# IotaWatt4_8.net
KiCad netlist of a schematic drawn in EAGLE
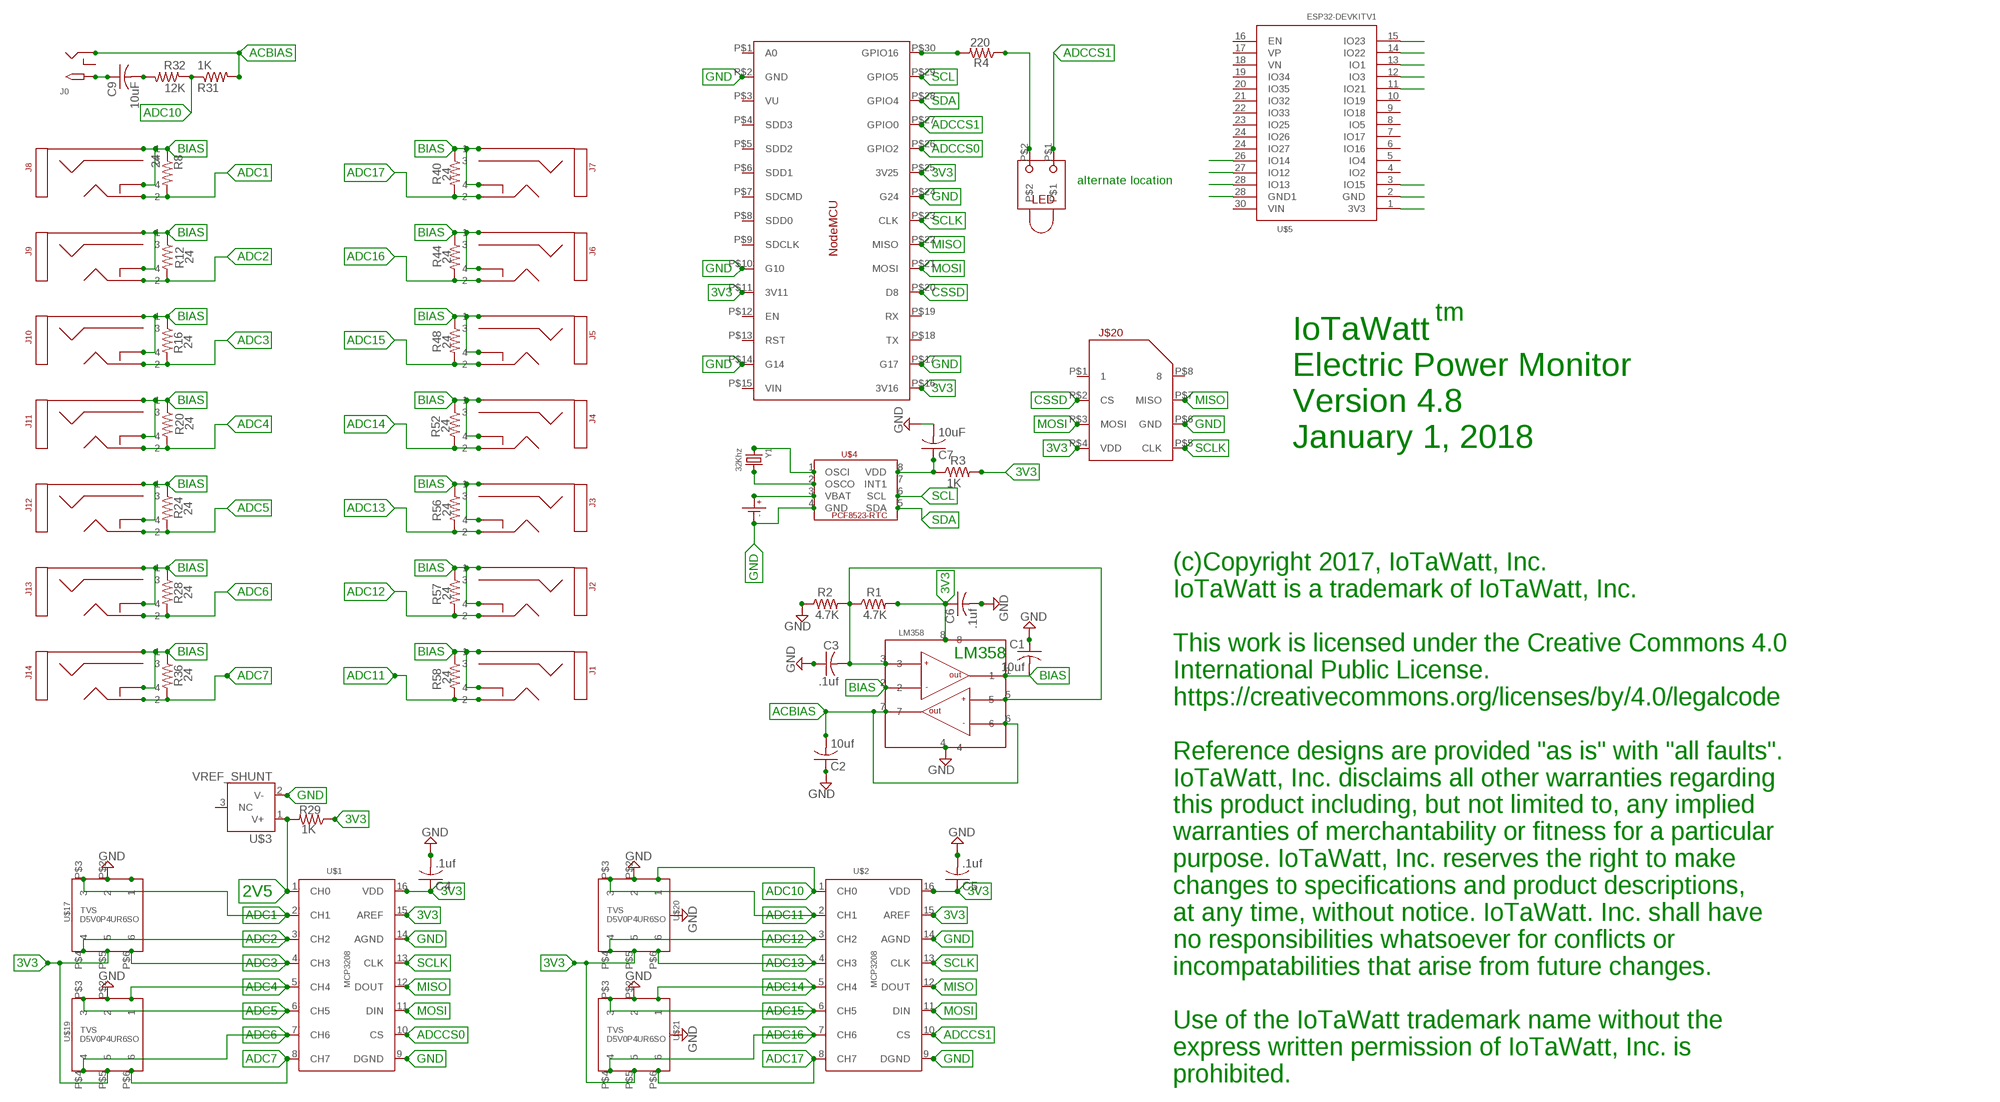
[diagram p0: schematic, sheet 1]

(export (version "E")
  (design (tool "Eeschema 10.0.6"))
  (components
    (comp (ref "C1")
      (value "10uf")
      (footprint "eagle-import:C0805")
      (libsource (lib "eagle-import") (part "C-USC0805"))
    )
    (comp (ref "C2")
      (value "10uf")
      (footprint "eagle-import:C0805")
      (libsource (lib "eagle-import") (part "C-USC0805"))
    )
    (comp (ref "C3")
      (value ".1uf")
      (footprint "eagle-import:C0805")
      (libsource (lib "eagle-import") (part "C-USC0805"))
    )
    (comp (ref "C4")
      (value ".1uf")
      (footprint "eagle-import:C0805")
      (libsource (lib "eagle-import") (part "C-USC0805"))
    )
    (comp (ref "C5")
      (value ".1uf")
      (footprint "eagle-import:C0805")
      (libsource (lib "eagle-import") (part "C-USC0805"))
    )
    (comp (ref "C6")
      (value ".1uf")
      (footprint "eagle-import:C0805")
      (libsource (lib "eagle-import") (part "C-USC0805"))
    )
    (comp (ref "C7")
      (value "10uF")
      (footprint "eagle-import:C0805")
      (libsource (lib "eagle-import") (part "C-USC0805"))
    )
    (comp (ref "C9")
      (value "10uF")
      (footprint "eagle-import:C0805")
      (libsource (lib "eagle-import") (part "C-USC0805"))
    )
    (comp (ref "J$20")
      (value "MICROSD_PUSH/PULL")
      (footprint "eagle-import:MICROSD")
      (libsource (lib "eagle-import") (part "MICROSD_PUSH/PULL"))
    )
    (comp (ref "J0")
      (value "2.1MMJACKSMT")
      (footprint "eagle-import:DCJACK_2MM_SMT")
      (libsource (lib "eagle-import") (part "2.1MMJACKSMT"))
    )
    (comp (ref "J1")
      (value "STEREO_SMD")
      (footprint "eagle-import:STEREO_SMT")
      (libsource (lib "eagle-import") (part "STEREO_SMD"))
    )
    (comp (ref "J2")
      (value "STEREO_SMD")
      (footprint "eagle-import:STEREO_SMT")
      (libsource (lib "eagle-import") (part "STEREO_SMD"))
    )
    (comp (ref "J3")
      (value "STEREO_SMD")
      (footprint "eagle-import:STEREO_SMT")
      (libsource (lib "eagle-import") (part "STEREO_SMD"))
    )
    (comp (ref "J4")
      (value "STEREO_SMD")
      (footprint "eagle-import:STEREO_SMT")
      (libsource (lib "eagle-import") (part "STEREO_SMD"))
    )
    (comp (ref "J5")
      (value "STEREO_SMD")
      (footprint "eagle-import:STEREO_SMT")
      (libsource (lib "eagle-import") (part "STEREO_SMD"))
    )
    (comp (ref "J6")
      (value "STEREO_SMD")
      (footprint "eagle-import:STEREO_SMT")
      (libsource (lib "eagle-import") (part "STEREO_SMD"))
    )
    (comp (ref "J7")
      (value "STEREO_SMD")
      (footprint "eagle-import:STEREO_SMT")
      (libsource (lib "eagle-import") (part "STEREO_SMD"))
    )
    (comp (ref "J8")
      (value "STEREO_SMD")
      (footprint "eagle-import:STEREO_SMT")
      (libsource (lib "eagle-import") (part "STEREO_SMD"))
    )
    (comp (ref "J9")
      (value "STEREO_SMD")
      (footprint "eagle-import:STEREO_SMT")
      (libsource (lib "eagle-import") (part "STEREO_SMD"))
    )
    (comp (ref "J10")
      (value "STEREO_SMD")
      (footprint "eagle-import:STEREO_SMT")
      (libsource (lib "eagle-import") (part "STEREO_SMD"))
    )
    (comp (ref "J11")
      (value "STEREO_SMD")
      (footprint "eagle-import:STEREO_SMT")
      (libsource (lib "eagle-import") (part "STEREO_SMD"))
    )
    (comp (ref "J12")
      (value "STEREO_SMD")
      (footprint "eagle-import:STEREO_SMT")
      (libsource (lib "eagle-import") (part "STEREO_SMD"))
    )
    (comp (ref "J13")
      (value "STEREO_SMD")
      (footprint "eagle-import:STEREO_SMT")
      (libsource (lib "eagle-import") (part "STEREO_SMD"))
    )
    (comp (ref "J14")
      (value "STEREO_SMD")
      (footprint "eagle-import:STEREO_SMT")
      (libsource (lib "eagle-import") (part "STEREO_SMD"))
    )
    (comp (ref "R1")
      (value "4.7K")
      (footprint "eagle-import:R0805")
      (libsource (lib "eagle-import") (part "R-US_R0805"))
    )
    (comp (ref "R2")
      (value "4.7K")
      (footprint "eagle-import:R0805")
      (libsource (lib "eagle-import") (part "R-US_R0805"))
    )
    (comp (ref "R3")
      (value "1K")
      (footprint "eagle-import:R0805")
      (libsource (lib "eagle-import") (part "R-US_R0805"))
    )
    (comp (ref "R4")
      (value "220")
      (footprint "eagle-import:R0805")
      (libsource (lib "eagle-import") (part "R-US_R0805"))
    )
    (comp (ref "R8")
      (value "24")
      (footprint "eagle-import:R0805")
      (libsource (lib "eagle-import") (part "R-US_R0805"))
    )
    (comp (ref "R12")
      (value "24")
      (footprint "eagle-import:R0805")
      (libsource (lib "eagle-import") (part "R-US_R0805"))
    )
    (comp (ref "R16")
      (value "24")
      (footprint "eagle-import:R0805")
      (libsource (lib "eagle-import") (part "R-US_R0805"))
    )
    (comp (ref "R20")
      (value "24")
      (footprint "eagle-import:R0805")
      (libsource (lib "eagle-import") (part "R-US_R0805"))
    )
    (comp (ref "R24")
      (value "24")
      (footprint "eagle-import:R0805")
      (libsource (lib "eagle-import") (part "R-US_R0805"))
    )
    (comp (ref "R28")
      (value "24")
      (footprint "eagle-import:R0805")
      (libsource (lib "eagle-import") (part "R-US_R0805"))
    )
    (comp (ref "R29")
      (value "1K")
      (footprint "eagle-import:R0805")
      (libsource (lib "eagle-import") (part "R-US_R0805"))
    )
    (comp (ref "R31")
      (value "1K")
      (footprint "eagle-import:R0805")
      (libsource (lib "eagle-import") (part "R-US_R0805"))
    )
    (comp (ref "R32")
      (value "12K")
      (footprint "eagle-import:R0805")
      (libsource (lib "eagle-import") (part "R-US_R0805"))
    )
    (comp (ref "R36")
      (value "24")
      (footprint "eagle-import:R0805")
      (libsource (lib "eagle-import") (part "R-US_R0805"))
    )
    (comp (ref "R40")
      (value "24")
      (footprint "eagle-import:R0805")
      (libsource (lib "eagle-import") (part "R-US_R0805"))
    )
    (comp (ref "R44")
      (value "24")
      (footprint "eagle-import:R0805")
      (libsource (lib "eagle-import") (part "R-US_R0805"))
    )
    (comp (ref "R48")
      (value "24")
      (footprint "eagle-import:R0805")
      (libsource (lib "eagle-import") (part "R-US_R0805"))
    )
    (comp (ref "R52")
      (value "24")
      (footprint "eagle-import:R0805")
      (libsource (lib "eagle-import") (part "R-US_R0805"))
    )
    (comp (ref "R56")
      (value "24")
      (footprint "eagle-import:R0805")
      (libsource (lib "eagle-import") (part "R-US_R0805"))
    )
    (comp (ref "R57")
      (value "24")
      (footprint "eagle-import:R0805")
      (libsource (lib "eagle-import") (part "R-US_R0805"))
    )
    (comp (ref "R58")
      (value "24")
      (footprint "eagle-import:R0805")
      (libsource (lib "eagle-import") (part "R-US_R0805"))
    )
    (comp (ref "U$1")
      (value "MCP3208")
      (footprint "eagle-import:SOIC_16")
      (libsource (lib "eagle-import") (part "MCP3208"))
    )
    (comp (ref "U$2")
      (value "MCP3208")
      (footprint "eagle-import:SOIC_16")
      (libsource (lib "eagle-import") (part "MCP3208"))
    )
    (comp (ref "U$3")
      (value "VREF_SHUNT")
      (footprint "eagle-import:SOT23_3")
      (libsource (lib "eagle-import") (part "VREF_SHUNT"))
    )
    (comp (ref "U$4")
      (value "PCF8523_RTC")
      (footprint "eagle-import:SOIC_8")
      (libsource (lib "eagle-import") (part "PCF8523_RTC"))
    )
    (comp (ref "U$5")
      (value "ESP32DEVKITV1")
      (footprint "eagle-import:ESP32-DEVKITV1")
      (libsource (lib "eagle-import") (part "ESP32DEVKITV1"))
    )
    (comp (ref "U$16")
      (value "NODEMCU")
      (footprint "eagle-import:NODEMCU")
      (libsource (lib "eagle-import") (part "NODEMCU"))
    )
    (comp (ref "U$17")
      (value "TVS_4CHAN_ARRAYSC-74")
      (footprint "eagle-import:SC-74")
      (libsource (lib "eagle-import") (part "TVS_4CHAN_ARRAYSC-74"))
    )
    (comp (ref "U$18")
      (value "CR1220SMD")
      (footprint "eagle-import:CR1220SMD")
      (libsource (lib "eagle-import") (part "CR1220SMD"))
    )
    (comp (ref "U$19")
      (value "TVS_4CHAN_ARRAYSC-74")
      (footprint "eagle-import:SC-74")
      (libsource (lib "eagle-import") (part "TVS_4CHAN_ARRAYSC-74"))
    )
    (comp (ref "U$20")
      (value "TVS_4CHAN_ARRAYSC-74")
      (footprint "eagle-import:SC-74")
      (libsource (lib "eagle-import") (part "TVS_4CHAN_ARRAYSC-74"))
    )
    (comp (ref "U$21")
      (value "TVS_4CHAN_ARRAYSC-74")
      (footprint "eagle-import:SC-74")
      (libsource (lib "eagle-import") (part "TVS_4CHAN_ARRAYSC-74"))
    )
    (comp (ref "U$22")
      (value "LM358_DUAL_OP-AMP")
      (footprint "eagle-import:SOIC_8")
      (libsource (lib "eagle-import") (part "LM358_DUAL_OP-AMP"))
    )
    (comp (ref "U$23")
      (value "LED_RT_TRH")
      (footprint "eagle-import:LED_TH_RT")
      (libsource (lib "eagle-import") (part "LED_RT_TRH"))
    )
    (comp (ref "Y1")
      (value "32Khz")
      (footprint "eagle-import:CRYSTAL_8X3.8")
      (libsource (lib "eagle-import") (part "CRYSTAL8X3.8SMT"))
    )
  )
  (nets
    (net (code "1") (name "/LED") (class "Default")
      (node (ref "R4") (pin "2") (pinfunction "2_2") (pintype "passive"))
      (node (ref "U$16") (pin "P$30") (pinfunction "GPIO16_P$30") (pintype "bidirectional"))
      (node (ref "U$5") (pin "15") (pinfunction "IO23_15") (pintype "bidirectional"))
    )
    (net (code "2") (name "2V5") (class "Default")
      (node (ref "R29") (pin "2") (pinfunction "2_2") (pintype "passive"))
      (node (ref "U$1") (pin "1") (pinfunction "CH0_1") (pintype "input"))
      (node (ref "U$3") (pin "1") (pinfunction "V+_1") (pintype "bidirectional"))
    )
    (net (code "3") (name "3V3") (class "Default")
      (node (ref "C4") (pin "1") (pinfunction "1_1") (pintype "passive"))
      (node (ref "C5") (pin "1") (pinfunction "1_1") (pintype "passive"))
      (node (ref "C6") (pin "1") (pinfunction "1_1") (pintype "passive"))
      (node (ref "J$20") (pin "P$4") (pinfunction "VDD_P$4") (pintype "bidirectional"))
      (node (ref "R1") (pin "2") (pinfunction "2_2") (pintype "passive"))
      (node (ref "R29") (pin "1") (pinfunction "1_1") (pintype "passive"))
      (node (ref "R3") (pin "2") (pinfunction "2_2") (pintype "passive"))
      (node (ref "U$1") (pin "15") (pinfunction "AREF_15") (pintype "input"))
      (node (ref "U$1") (pin "16") (pinfunction "VDD_16") (pintype "bidirectional"))
      (node (ref "U$16") (pin "P$11") (pinfunction "3V11_P$11") (pintype "bidirectional"))
      (node (ref "U$16") (pin "P$16") (pinfunction "3V16_P$16") (pintype "bidirectional"))
      (node (ref "U$16") (pin "P$25") (pinfunction "3V25_P$25") (pintype "bidirectional"))
      (node (ref "U$17") (pin "P$5") (pinfunction "5_P$5") (pintype "bidirectional"))
      (node (ref "U$19") (pin "P$5") (pinfunction "5_P$5") (pintype "bidirectional"))
      (node (ref "U$2") (pin "15") (pinfunction "AREF_15") (pintype "input"))
      (node (ref "U$2") (pin "16") (pinfunction "VDD_16") (pintype "bidirectional"))
      (node (ref "U$20") (pin "P$5") (pinfunction "5_P$5") (pintype "bidirectional"))
      (node (ref "U$21") (pin "P$5") (pinfunction "5_P$5") (pintype "bidirectional"))
      (node (ref "U$22") (pin "8") (pinfunction "8_8") (pintype "bidirectional"))
      (node (ref "U$5") (pin "1") (pinfunction "3V3_1") (pintype "bidirectional"))
    )
    (net (code "4") (name "ACBIAS") (class "Default")
      (node (ref "C2") (pin "2") (pinfunction "2_2") (pintype "passive"))
      (node (ref "J0") (pin "GND") (pinfunction "RING_GND") (pintype "bidirectional"))
      (node (ref "R31") (pin "2") (pinfunction "2_2") (pintype "passive"))
      (node (ref "U$22") (pin "6") (pinfunction "6_6") (pintype "bidirectional"))
      (node (ref "U$22") (pin "7") (pinfunction "7_7") (pintype "bidirectional"))
    )
    (net (code "5") (name "ADC1") (class "Default")
      (node (ref "J8") (pin "P$2") (pinfunction "2_P$2") (pintype "bidirectional"))
      (node (ref "R8") (pin "2") (pinfunction "2_2") (pintype "passive"))
      (node (ref "U$1") (pin "2") (pinfunction "CH1_2") (pintype "input"))
      (node (ref "U$17") (pin "P$3") (pinfunction "3_P$3") (pintype "bidirectional"))
    )
    (net (code "6") (name "ADC2") (class "Default")
      (node (ref "J9") (pin "P$2") (pinfunction "2_P$2") (pintype "bidirectional"))
      (node (ref "R12") (pin "2") (pinfunction "2_2") (pintype "passive"))
      (node (ref "U$1") (pin "3") (pinfunction "CH2_3") (pintype "input"))
      (node (ref "U$17") (pin "P$4") (pinfunction "4_P$4") (pintype "bidirectional"))
    )
    (net (code "7") (name "ADC3") (class "Default")
      (node (ref "J10") (pin "P$2") (pinfunction "2_P$2") (pintype "bidirectional"))
      (node (ref "R16") (pin "2") (pinfunction "2_2") (pintype "passive"))
      (node (ref "U$1") (pin "4") (pinfunction "CH3_4") (pintype "input"))
      (node (ref "U$17") (pin "P$6") (pinfunction "6_P$6") (pintype "bidirectional"))
    )
    (net (code "8") (name "ADC4") (class "Default")
      (node (ref "J11") (pin "P$2") (pinfunction "2_P$2") (pintype "bidirectional"))
      (node (ref "R20") (pin "2") (pinfunction "2_2") (pintype "passive"))
      (node (ref "U$1") (pin "5") (pinfunction "CH4_5") (pintype "bidirectional"))
      (node (ref "U$19") (pin "P$1") (pinfunction "1_P$1") (pintype "bidirectional"))
    )
    (net (code "9") (name "ADC5") (class "Default")
      (node (ref "J12") (pin "P$2") (pinfunction "2_P$2") (pintype "bidirectional"))
      (node (ref "R24") (pin "2") (pinfunction "2_2") (pintype "passive"))
      (node (ref "U$1") (pin "6") (pinfunction "CH5_6") (pintype "bidirectional"))
      (node (ref "U$19") (pin "P$3") (pinfunction "3_P$3") (pintype "bidirectional"))
    )
    (net (code "10") (name "ADC6") (class "Default")
      (node (ref "J13") (pin "P$2") (pinfunction "2_P$2") (pintype "bidirectional"))
      (node (ref "R28") (pin "2") (pinfunction "2_2") (pintype "passive"))
      (node (ref "U$1") (pin "7") (pinfunction "CH6_7") (pintype "input"))
      (node (ref "U$19") (pin "P$4") (pinfunction "4_P$4") (pintype "bidirectional"))
    )
    (net (code "11") (name "ADC7") (class "Default")
      (node (ref "J14") (pin "P$2") (pinfunction "2_P$2") (pintype "bidirectional"))
      (node (ref "R36") (pin "2") (pinfunction "2_2") (pintype "passive"))
      (node (ref "U$1") (pin "8") (pinfunction "CH7_8") (pintype "bidirectional"))
      (node (ref "U$19") (pin "P$6") (pinfunction "6_P$6") (pintype "bidirectional"))
    )
    (net (code "12") (name "ADC10") (class "Default")
      (node (ref "R31") (pin "1") (pinfunction "1_1") (pintype "passive"))
      (node (ref "R32") (pin "1") (pinfunction "1_1") (pintype "passive"))
      (node (ref "U$2") (pin "1") (pinfunction "CH0_1") (pintype "input"))
      (node (ref "U$20") (pin "P$1") (pinfunction "1_P$1") (pintype "bidirectional"))
    )
    (net (code "13") (name "ADC11") (class "Default")
      (node (ref "J1") (pin "P$2") (pinfunction "2_P$2") (pintype "bidirectional"))
      (node (ref "R58") (pin "2") (pinfunction "2_2") (pintype "passive"))
      (node (ref "U$2") (pin "2") (pinfunction "CH1_2") (pintype "input"))
      (node (ref "U$20") (pin "P$3") (pinfunction "3_P$3") (pintype "bidirectional"))
    )
    (net (code "14") (name "ADC12") (class "Default")
      (node (ref "J2") (pin "P$2") (pinfunction "2_P$2") (pintype "bidirectional"))
      (node (ref "R57") (pin "2") (pinfunction "2_2") (pintype "passive"))
      (node (ref "U$2") (pin "3") (pinfunction "CH2_3") (pintype "input"))
      (node (ref "U$20") (pin "P$4") (pinfunction "4_P$4") (pintype "bidirectional"))
    )
    (net (code "15") (name "ADC13") (class "Default")
      (node (ref "J3") (pin "P$2") (pinfunction "2_P$2") (pintype "bidirectional"))
      (node (ref "R56") (pin "2") (pinfunction "2_2") (pintype "passive"))
      (node (ref "U$2") (pin "4") (pinfunction "CH3_4") (pintype "input"))
      (node (ref "U$20") (pin "P$6") (pinfunction "6_P$6") (pintype "bidirectional"))
    )
    (net (code "16") (name "ADC14") (class "Default")
      (node (ref "J4") (pin "P$2") (pinfunction "2_P$2") (pintype "bidirectional"))
      (node (ref "R52") (pin "2") (pinfunction "2_2") (pintype "passive"))
      (node (ref "U$2") (pin "5") (pinfunction "CH4_5") (pintype "bidirectional"))
      (node (ref "U$21") (pin "P$1") (pinfunction "1_P$1") (pintype "bidirectional"))
    )
    (net (code "17") (name "ADC15") (class "Default")
      (node (ref "J5") (pin "P$2") (pinfunction "2_P$2") (pintype "bidirectional"))
      (node (ref "R48") (pin "2") (pinfunction "2_2") (pintype "passive"))
      (node (ref "U$2") (pin "6") (pinfunction "CH5_6") (pintype "bidirectional"))
      (node (ref "U$21") (pin "P$3") (pinfunction "3_P$3") (pintype "bidirectional"))
    )
    (net (code "18") (name "ADC16") (class "Default")
      (node (ref "J6") (pin "P$2") (pinfunction "2_P$2") (pintype "bidirectional"))
      (node (ref "R44") (pin "2") (pinfunction "2_2") (pintype "passive"))
      (node (ref "U$2") (pin "7") (pinfunction "CH6_7") (pintype "input"))
      (node (ref "U$21") (pin "P$4") (pinfunction "4_P$4") (pintype "bidirectional"))
    )
    (net (code "19") (name "ADC17") (class "Default")
      (node (ref "J7") (pin "P$2") (pinfunction "2_P$2") (pintype "bidirectional"))
      (node (ref "R40") (pin "2") (pinfunction "2_2") (pintype "passive"))
      (node (ref "U$2") (pin "8") (pinfunction "CH7_8") (pintype "bidirectional"))
      (node (ref "U$21") (pin "P$6") (pinfunction "6_P$6") (pintype "bidirectional"))
    )
    (net (code "20") (name "ADCCS0") (class "Default")
      (node (ref "U$1") (pin "10") (pinfunction "CS_10") (pintype "input"))
      (node (ref "U$16") (pin "P$26") (pinfunction "GPIO2_P$26") (pintype "bidirectional"))
      (node (ref "U$5") (pin "11") (pinfunction "IO21_11") (pintype "bidirectional"))
    )
    (net (code "21") (name "ADCCS1") (class "Default")
      (node (ref "U$16") (pin "P$27") (pinfunction "GPIO0_P$27") (pintype "bidirectional"))
      (node (ref "U$2") (pin "10") (pinfunction "CS_10") (pintype "input"))
      (node (ref "U$23") (pin "P$1") (pinfunction "P$1_P$1") (pintype "bidirectional"))
      (node (ref "U$5") (pin "12") (pinfunction "IO3_12") (pintype "bidirectional"))
    )
    (net (code "22") (name "BIAS") (class "Default")
      (node (ref "C1") (pin "2") (pinfunction "2_2") (pintype "passive"))
      (node (ref "J1") (pin "P$1") (pinfunction "1_P$1") (pintype "bidirectional"))
      (node (ref "J1") (pin "P$4") (pinfunction "4_P$4") (pintype "bidirectional"))
      (node (ref "J10") (pin "P$1") (pinfunction "1_P$1") (pintype "bidirectional"))
      (node (ref "J10") (pin "P$4") (pinfunction "4_P$4") (pintype "bidirectional"))
      (node (ref "J11") (pin "P$1") (pinfunction "1_P$1") (pintype "bidirectional"))
      (node (ref "J11") (pin "P$4") (pinfunction "4_P$4") (pintype "bidirectional"))
      (node (ref "J12") (pin "P$1") (pinfunction "1_P$1") (pintype "bidirectional"))
      (node (ref "J12") (pin "P$4") (pinfunction "4_P$4") (pintype "bidirectional"))
      (node (ref "J13") (pin "P$1") (pinfunction "1_P$1") (pintype "bidirectional"))
      (node (ref "J13") (pin "P$4") (pinfunction "4_P$4") (pintype "bidirectional"))
      (node (ref "J14") (pin "P$1") (pinfunction "1_P$1") (pintype "bidirectional"))
      (node (ref "J14") (pin "P$4") (pinfunction "4_P$4") (pintype "bidirectional"))
      (node (ref "J2") (pin "P$1") (pinfunction "1_P$1") (pintype "bidirectional"))
      (node (ref "J2") (pin "P$4") (pinfunction "4_P$4") (pintype "bidirectional"))
      (node (ref "J3") (pin "P$1") (pinfunction "1_P$1") (pintype "bidirectional"))
      (node (ref "J3") (pin "P$4") (pinfunction "4_P$4") (pintype "bidirectional"))
      (node (ref "J4") (pin "P$1") (pinfunction "1_P$1") (pintype "bidirectional"))
      (node (ref "J4") (pin "P$4") (pinfunction "4_P$4") (pintype "bidirectional"))
      (node (ref "J5") (pin "P$1") (pinfunction "1_P$1") (pintype "bidirectional"))
      (node (ref "J5") (pin "P$4") (pinfunction "4_P$4") (pintype "bidirectional"))
      (node (ref "J6") (pin "P$1") (pinfunction "1_P$1") (pintype "bidirectional"))
      (node (ref "J6") (pin "P$4") (pinfunction "4_P$4") (pintype "bidirectional"))
      (node (ref "J7") (pin "P$1") (pinfunction "1_P$1") (pintype "bidirectional"))
      (node (ref "J7") (pin "P$4") (pinfunction "4_P$4") (pintype "bidirectional"))
      (node (ref "J8") (pin "P$1") (pinfunction "1_P$1") (pintype "bidirectional"))
      (node (ref "J8") (pin "P$4") (pinfunction "4_P$4") (pintype "bidirectional"))
      (node (ref "J9") (pin "P$1") (pinfunction "1_P$1") (pintype "bidirectional"))
      (node (ref "J9") (pin "P$4") (pinfunction "4_P$4") (pintype "bidirectional"))
      (node (ref "R12") (pin "1") (pinfunction "1_1") (pintype "passive"))
      (node (ref "R16") (pin "1") (pinfunction "1_1") (pintype "passive"))
      (node (ref "R20") (pin "1") (pinfunction "1_1") (pintype "passive"))
      (node (ref "R24") (pin "1") (pinfunction "1_1") (pintype "passive"))
      (node (ref "R28") (pin "1") (pinfunction "1_1") (pintype "passive"))
      (node (ref "R36") (pin "1") (pinfunction "1_1") (pintype "passive"))
      (node (ref "R40") (pin "1") (pinfunction "1_1") (pintype "passive"))
      (node (ref "R44") (pin "1") (pinfunction "1_1") (pintype "passive"))
      (node (ref "R48") (pin "1") (pinfunction "1_1") (pintype "passive"))
      (node (ref "R52") (pin "1") (pinfunction "1_1") (pintype "passive"))
      (node (ref "R56") (pin "1") (pinfunction "1_1") (pintype "passive"))
      (node (ref "R57") (pin "1") (pinfunction "1_1") (pintype "passive"))
      (node (ref "R58") (pin "1") (pinfunction "1_1") (pintype "passive"))
      (node (ref "R8") (pin "1") (pinfunction "1_1") (pintype "passive"))
      (node (ref "U$22") (pin "1") (pinfunction "1_1") (pintype "bidirectional"))
      (node (ref "U$22") (pin "2") (pinfunction "2_2") (pintype "bidirectional"))
    )
    (net (code "23") (name "CSSD") (class "Default")
      (node (ref "J$20") (pin "P$2") (pinfunction "CS_P$2") (pintype "bidirectional"))
      (node (ref "U$16") (pin "P$20") (pinfunction "D8_P$20") (pintype "bidirectional"))
      (node (ref "U$5") (pin "3") (pinfunction "IO15_3") (pintype "bidirectional"))
    )
    (net (code "24") (name "GND") (class "Default")
      (node (ref "C1") (pin "1") (pinfunction "1_1") (pintype "passive"))
      (node (ref "C2") (pin "1") (pinfunction "1_1") (pintype "passive"))
      (node (ref "C3") (pin "1") (pinfunction "1_1") (pintype "passive"))
      (node (ref "C4") (pin "2") (pinfunction "2_2") (pintype "passive"))
      (node (ref "C5") (pin "2") (pinfunction "2_2") (pintype "passive"))
      (node (ref "C6") (pin "2") (pinfunction "2_2") (pintype "passive"))
      (node (ref "C7") (pin "2") (pinfunction "2_2") (pintype "passive"))
      (node (ref "J$20") (pin "P$6") (pinfunction "GND_P$6") (pintype "bidirectional"))
      (node (ref "R2") (pin "1") (pinfunction "1_1") (pintype "passive"))
      (node (ref "U$1") (pin "14") (pinfunction "AGND_14") (pintype "input"))
      (node (ref "U$1") (pin "9") (pinfunction "DGND_9") (pintype "bidirectional"))
      (node (ref "U$16") (pin "P$10") (pinfunction "G10_P$10") (pintype "bidirectional"))
      (node (ref "U$16") (pin "P$14") (pinfunction "G14_P$14") (pintype "bidirectional"))
      (node (ref "U$16") (pin "P$17") (pinfunction "G17_P$17") (pintype "bidirectional"))
      (node (ref "U$16") (pin "P$2") (pinfunction "GND_P$2") (pintype "bidirectional"))
      (node (ref "U$16") (pin "P$24") (pinfunction "G24_P$24") (pintype "bidirectional"))
      (node (ref "U$17") (pin "P$2") (pinfunction "2_P$2") (pintype "bidirectional"))
      (node (ref "U$18") (pin "P-") (pinfunction "P$-_P-") (pintype "bidirectional"))
      (node (ref "U$19") (pin "P$2") (pinfunction "2_P$2") (pintype "bidirectional"))
      (node (ref "U$2") (pin "14") (pinfunction "AGND_14") (pintype "input"))
      (node (ref "U$2") (pin "9") (pinfunction "DGND_9") (pintype "bidirectional"))
      (node (ref "U$20") (pin "P$2") (pinfunction "2_P$2") (pintype "bidirectional"))
      (node (ref "U$21") (pin "P$2") (pinfunction "2_P$2") (pintype "bidirectional"))
      (node (ref "U$22") (pin "4") (pinfunction "4_4") (pintype "bidirectional"))
      (node (ref "U$3") (pin "2") (pinfunction "V-_2") (pintype "bidirectional"))
      (node (ref "U$4") (pin "4") (pinfunction "GND_4") (pintype "bidirectional"))
      (node (ref "U$5") (pin "2") (pinfunction "GND_2") (pintype "bidirectional"))
      (node (ref "U$5") (pin "28") (pinfunction "GND1_28") (pintype "bidirectional"))
    )
    (net (code "25") (name "MISO") (class "Default")
      (node (ref "J$20") (pin "P$7") (pinfunction "MISO_P$7") (pintype "bidirectional"))
      (node (ref "U$1") (pin "12") (pinfunction "DOUT_12") (pintype "bidirectional"))
      (node (ref "U$16") (pin "P$22") (pinfunction "MISO_P$22") (pintype "bidirectional"))
      (node (ref "U$2") (pin "12") (pinfunction "DOUT_12") (pintype "bidirectional"))
      (node (ref "U$5") (pin "27") (pinfunction "IO12_27") (pintype "bidirectional"))
    )
    (net (code "26") (name "MOSI") (class "Default")
      (node (ref "J$20") (pin "P$3") (pinfunction "MOSI_P$3") (pintype "bidirectional"))
      (node (ref "U$1") (pin "11") (pinfunction "DIN_11") (pintype "input"))
      (node (ref "U$16") (pin "P$21") (pinfunction "MOSI_P$21") (pintype "bidirectional"))
      (node (ref "U$2") (pin "11") (pinfunction "DIN_11") (pintype "input"))
      (node (ref "U$5") (pin "28") (pinfunction "IO13_28") (pintype "bidirectional"))
    )
    (net (code "27") (name "Net-(C3-Pad2)") (class "Default")
      (node (ref "C3") (pin "2") (pinfunction "2_2") (pintype "passive"))
      (node (ref "R1") (pin "1") (pinfunction "1_1") (pintype "passive"))
      (node (ref "R2") (pin "2") (pinfunction "2_2") (pintype "passive"))
      (node (ref "U$22") (pin "3") (pinfunction "3_3") (pintype "bidirectional"))
      (node (ref "U$22") (pin "5") (pinfunction "5_5") (pintype "bidirectional"))
    )
    (net (code "28") (name "Net-(C9-Pad2)") (class "Default")
      (node (ref "C9") (pin "2") (pinfunction "2_2") (pintype "passive"))
      (node (ref "R32") (pin "2") (pinfunction "2_2") (pintype "passive"))
    )
    (net (code "29") (name "Net-(J0-TIP)") (class "Default")
      (node (ref "C9") (pin "1") (pinfunction "1_1") (pintype "passive"))
      (node (ref "J0") (pin "PWR2") (pinfunction "TIP_PWR2") (pintype "bidirectional"))
    )
    (net (code "30") (name "Net-(R4-Pad1)") (class "Default")
      (node (ref "R4") (pin "1") (pinfunction "1_1") (pintype "passive"))
      (node (ref "U$23") (pin "P$2") (pinfunction "P$2_P$2") (pintype "bidirectional"))
    )
    (net (code "31") (name "Net-(U$4-OSCI)") (class "Default")
      (node (ref "U$4") (pin "1") (pinfunction "OSCI_1") (pintype "bidirectional"))
      (node (ref "Y1") (pin "P$1") (pinfunction "1_P$1") (pintype "passive"))
    )
    (net (code "32") (name "Net-(U$4-OSCO)") (class "Default")
      (node (ref "U$4") (pin "2") (pinfunction "OSCO_2") (pintype "bidirectional"))
      (node (ref "Y1") (pin "P$4") (pinfunction "2_P$4") (pintype "passive"))
    )
    (net (code "33") (name "Net-(U$4-VDD)") (class "Default")
      (node (ref "C7") (pin "1") (pinfunction "1_1") (pintype "passive"))
      (node (ref "R3") (pin "1") (pinfunction "1_1") (pintype "passive"))
      (node (ref "U$4") (pin "8") (pinfunction "VDD_8") (pintype "bidirectional"))
    )
    (net (code "34") (name "Net-(U$18-P$+)") (class "Default")
      (node (ref "U$18") (pin "P+") (pinfunction "P$+_P+") (pintype "bidirectional"))
      (node (ref "U$4") (pin "3") (pinfunction "VBAT_3") (pintype "bidirectional"))
    )
    (net (code "35") (name "SCL") (class "Default")
      (node (ref "U$16") (pin "P$29") (pinfunction "GPIO5_P$29") (pintype "bidirectional"))
      (node (ref "U$4") (pin "6") (pinfunction "SCL_6") (pintype "bidirectional"))
      (node (ref "U$5") (pin "14") (pinfunction "IO22_14") (pintype "bidirectional"))
    )
    (net (code "36") (name "SCLK") (class "Default")
      (node (ref "J$20") (pin "P$5") (pinfunction "CLK_P$5") (pintype "bidirectional"))
      (node (ref "U$1") (pin "13") (pinfunction "CLK_13") (pintype "input"))
      (node (ref "U$16") (pin "P$23") (pinfunction "CLK_P$23") (pintype "bidirectional"))
      (node (ref "U$2") (pin "13") (pinfunction "CLK_13") (pintype "input"))
      (node (ref "U$5") (pin "26") (pinfunction "IO14_26") (pintype "bidirectional"))
    )
    (net (code "37") (name "SDA") (class "Default")
      (node (ref "U$16") (pin "P$28") (pinfunction "GPIO4_P$28") (pintype "bidirectional"))
      (node (ref "U$4") (pin "5") (pinfunction "SDA_5") (pintype "bidirectional"))
      (node (ref "U$5") (pin "13") (pinfunction "IO1_13") (pintype "bidirectional"))
    )
    (net (code "38") (name "unconnected-(J$20-1-PadP$1)") (class "Default")
      (node (ref "J$20") (pin "P$1") (pinfunction "1_P$1") (pintype "bidirectional"))
    )
    (net (code "39") (name "unconnected-(J$20-8-PadP$8)") (class "Default")
      (node (ref "J$20") (pin "P$8") (pinfunction "8_P$8") (pintype "bidirectional"))
    )
    (net (code "40") (name "unconnected-(J0-RING_SW-PadGNDBREAK)") (class "Default")
      (node (ref "J0") (pin "GNDBREAK") (pinfunction "RING_SW_GNDBREAK") (pintype "bidirectional"))
    )
    (net (code "41") (name "unconnected-(J1-3-PadP$3)") (class "Default")
      (node (ref "J1") (pin "P$3") (pinfunction "3_P$3") (pintype "bidirectional"))
    )
    (net (code "42") (name "unconnected-(J2-3-PadP$3)") (class "Default")
      (node (ref "J2") (pin "P$3") (pinfunction "3_P$3") (pintype "bidirectional"))
    )
    (net (code "43") (name "unconnected-(J3-3-PadP$3)") (class "Default")
      (node (ref "J3") (pin "P$3") (pinfunction "3_P$3") (pintype "bidirectional"))
    )
    (net (code "44") (name "unconnected-(J4-3-PadP$3)") (class "Default")
      (node (ref "J4") (pin "P$3") (pinfunction "3_P$3") (pintype "bidirectional"))
    )
    (net (code "45") (name "unconnected-(J5-3-PadP$3)") (class "Default")
      (node (ref "J5") (pin "P$3") (pinfunction "3_P$3") (pintype "bidirectional"))
    )
    (net (code "46") (name "unconnected-(J6-3-PadP$3)") (class "Default")
      (node (ref "J6") (pin "P$3") (pinfunction "3_P$3") (pintype "bidirectional"))
    )
    (net (code "47") (name "unconnected-(J7-3-PadP$3)") (class "Default")
      (node (ref "J7") (pin "P$3") (pinfunction "3_P$3") (pintype "bidirectional"))
    )
    (net (code "48") (name "unconnected-(J8-3-PadP$3)") (class "Default")
      (node (ref "J8") (pin "P$3") (pinfunction "3_P$3") (pintype "bidirectional"))
    )
    (net (code "49") (name "unconnected-(J9-3-PadP$3)") (class "Default")
      (node (ref "J9") (pin "P$3") (pinfunction "3_P$3") (pintype "bidirectional"))
    )
    (net (code "50") (name "unconnected-(J10-3-PadP$3)") (class "Default")
      (node (ref "J10") (pin "P$3") (pinfunction "3_P$3") (pintype "bidirectional"))
    )
    (net (code "51") (name "unconnected-(J11-3-PadP$3)") (class "Default")
      (node (ref "J11") (pin "P$3") (pinfunction "3_P$3") (pintype "bidirectional"))
    )
    (net (code "52") (name "unconnected-(J12-3-PadP$3)") (class "Default")
      (node (ref "J12") (pin "P$3") (pinfunction "3_P$3") (pintype "bidirectional"))
    )
    (net (code "53") (name "unconnected-(J13-3-PadP$3)") (class "Default")
      (node (ref "J13") (pin "P$3") (pinfunction "3_P$3") (pintype "bidirectional"))
    )
    (net (code "54") (name "unconnected-(J14-3-PadP$3)") (class "Default")
      (node (ref "J14") (pin "P$3") (pinfunction "3_P$3") (pintype "bidirectional"))
    )
    (net (code "55") (name "unconnected-(U$3-NC-Pad3)") (class "Default")
      (node (ref "U$3") (pin "3") (pinfunction "NC_3") (pintype "bidirectional"))
    )
    (net (code "56") (name "unconnected-(U$4-INT1-Pad7)") (class "Default")
      (node (ref "U$4") (pin "7") (pinfunction "INT1_7") (pintype "bidirectional"))
    )
    (net (code "57") (name "unconnected-(U$5-EN-Pad16)") (class "Default")
      (node (ref "U$5") (pin "16") (pinfunction "EN_16") (pintype "bidirectional"))
    )
    (net (code "58") (name "unconnected-(U$5-IO2-Pad4)") (class "Default")
      (node (ref "U$5") (pin "4") (pinfunction "IO2_4") (pintype "bidirectional"))
    )
    (net (code "59") (name "unconnected-(U$5-IO4-Pad5)") (class "Default")
      (node (ref "U$5") (pin "5") (pinfunction "IO4_5") (pintype "bidirectional"))
    )
    (net (code "60") (name "unconnected-(U$5-IO5-Pad8)") (class "Default")
      (node (ref "U$5") (pin "8") (pinfunction "IO5_8") (pintype "bidirectional"))
    )
    (net (code "61") (name "unconnected-(U$5-IO16-Pad6)") (class "Default")
      (node (ref "U$5") (pin "6") (pinfunction "IO16_6") (pintype "bidirectional"))
    )
    (net (code "62") (name "unconnected-(U$5-IO17-Pad7)") (class "Default")
      (node (ref "U$5") (pin "7") (pinfunction "IO17_7") (pintype "bidirectional"))
    )
    (net (code "63") (name "unconnected-(U$5-IO18-Pad9)") (class "Default")
      (node (ref "U$5") (pin "9") (pinfunction "IO18_9") (pintype "bidirectional"))
    )
    (net (code "64") (name "unconnected-(U$5-IO19-Pad10)") (class "Default")
      (node (ref "U$5") (pin "10") (pinfunction "IO19_10") (pintype "bidirectional"))
    )
    (net (code "65") (name "unconnected-(U$5-IO25-Pad23)") (class "Default")
      (node (ref "U$5") (pin "23") (pinfunction "IO25_23") (pintype "bidirectional"))
    )
    (net (code "66") (name "unconnected-(U$5-IO26-Pad24)") (class "Default")
      (node (ref "U$5") (pin "24") (pinfunction "IO26_24") (pintype "bidirectional"))
    )
    (net (code "67") (name "unconnected-(U$5-IO27-Pad24)") (class "Default")
      (node (ref "U$5") (pin "24") (pinfunction "IO27_24") (pintype "bidirectional"))
    )
    (net (code "68") (name "unconnected-(U$5-IO32-Pad21)") (class "Default")
      (node (ref "U$5") (pin "21") (pinfunction "IO32_21") (pintype "bidirectional"))
    )
    (net (code "69") (name "unconnected-(U$5-IO33-Pad22)") (class "Default")
      (node (ref "U$5") (pin "22") (pinfunction "IO33_22") (pintype "bidirectional"))
    )
    (net (code "70") (name "unconnected-(U$5-IO34-Pad19)") (class "Default")
      (node (ref "U$5") (pin "19") (pinfunction "IO34_19") (pintype "bidirectional"))
    )
    (net (code "71") (name "unconnected-(U$5-IO35-Pad20)") (class "Default")
      (node (ref "U$5") (pin "20") (pinfunction "IO35_20") (pintype "bidirectional"))
    )
    (net (code "72") (name "unconnected-(U$5-VIN-Pad30)") (class "Default")
      (node (ref "U$5") (pin "30") (pinfunction "VIN_30") (pintype "bidirectional"))
    )
    (net (code "73") (name "unconnected-(U$5-VN-Pad18)") (class "Default")
      (node (ref "U$5") (pin "18") (pinfunction "VN_18") (pintype "bidirectional"))
    )
    (net (code "74") (name "unconnected-(U$5-VP-Pad17)") (class "Default")
      (node (ref "U$5") (pin "17") (pinfunction "VP_17") (pintype "bidirectional"))
    )
    (net (code "75") (name "unconnected-(U$16-A0-PadP$1)") (class "Default")
      (node (ref "U$16") (pin "P$1") (pinfunction "A0_P$1") (pintype "bidirectional"))
    )
    (net (code "76") (name "unconnected-(U$16-EN-PadP$12)") (class "Default")
      (node (ref "U$16") (pin "P$12") (pinfunction "EN_P$12") (pintype "bidirectional"))
    )
    (net (code "77") (name "unconnected-(U$16-RST-PadP$13)") (class "Default")
      (node (ref "U$16") (pin "P$13") (pinfunction "RST_P$13") (pintype "bidirectional"))
    )
    (net (code "78") (name "unconnected-(U$16-RX-PadP$19)") (class "Default")
      (node (ref "U$16") (pin "P$19") (pinfunction "RX_P$19") (pintype "bidirectional"))
    )
    (net (code "79") (name "unconnected-(U$16-SDCLK-PadP$9)") (class "Default")
      (node (ref "U$16") (pin "P$9") (pinfunction "SDCLK_P$9") (pintype "bidirectional"))
    )
    (net (code "80") (name "unconnected-(U$16-SDCMD-PadP$7)") (class "Default")
      (node (ref "U$16") (pin "P$7") (pinfunction "SDCMD_P$7") (pintype "bidirectional"))
    )
    (net (code "81") (name "unconnected-(U$16-SDD0-PadP$8)") (class "Default")
      (node (ref "U$16") (pin "P$8") (pinfunction "SDD0_P$8") (pintype "bidirectional"))
    )
    (net (code "82") (name "unconnected-(U$16-SDD1-PadP$6)") (class "Default")
      (node (ref "U$16") (pin "P$6") (pinfunction "SDD1_P$6") (pintype "bidirectional"))
    )
    (net (code "83") (name "unconnected-(U$16-SDD2-PadP$5)") (class "Default")
      (node (ref "U$16") (pin "P$5") (pinfunction "SDD2_P$5") (pintype "bidirectional"))
    )
    (net (code "84") (name "unconnected-(U$16-SDD3-PadP$4)") (class "Default")
      (node (ref "U$16") (pin "P$4") (pinfunction "SDD3_P$4") (pintype "bidirectional"))
    )
    (net (code "85") (name "unconnected-(U$16-TX-PadP$18)") (class "Default")
      (node (ref "U$16") (pin "P$18") (pinfunction "TX_P$18") (pintype "bidirectional"))
    )
    (net (code "86") (name "unconnected-(U$16-VIN-PadP$15)") (class "Default")
      (node (ref "U$16") (pin "P$15") (pinfunction "VIN_P$15") (pintype "bidirectional"))
    )
    (net (code "87") (name "unconnected-(U$16-VU-PadP$3)") (class "Default")
      (node (ref "U$16") (pin "P$3") (pinfunction "VU_P$3") (pintype "bidirectional"))
    )
    (net (code "88") (name "unconnected-(U$17-1-PadP$1)") (class "Default")
      (node (ref "U$17") (pin "P$1") (pinfunction "1_P$1") (pintype "bidirectional"))
    )
  )
)
